# PSU.net
KiCad netlist of a schematic drawn in Altium Designer
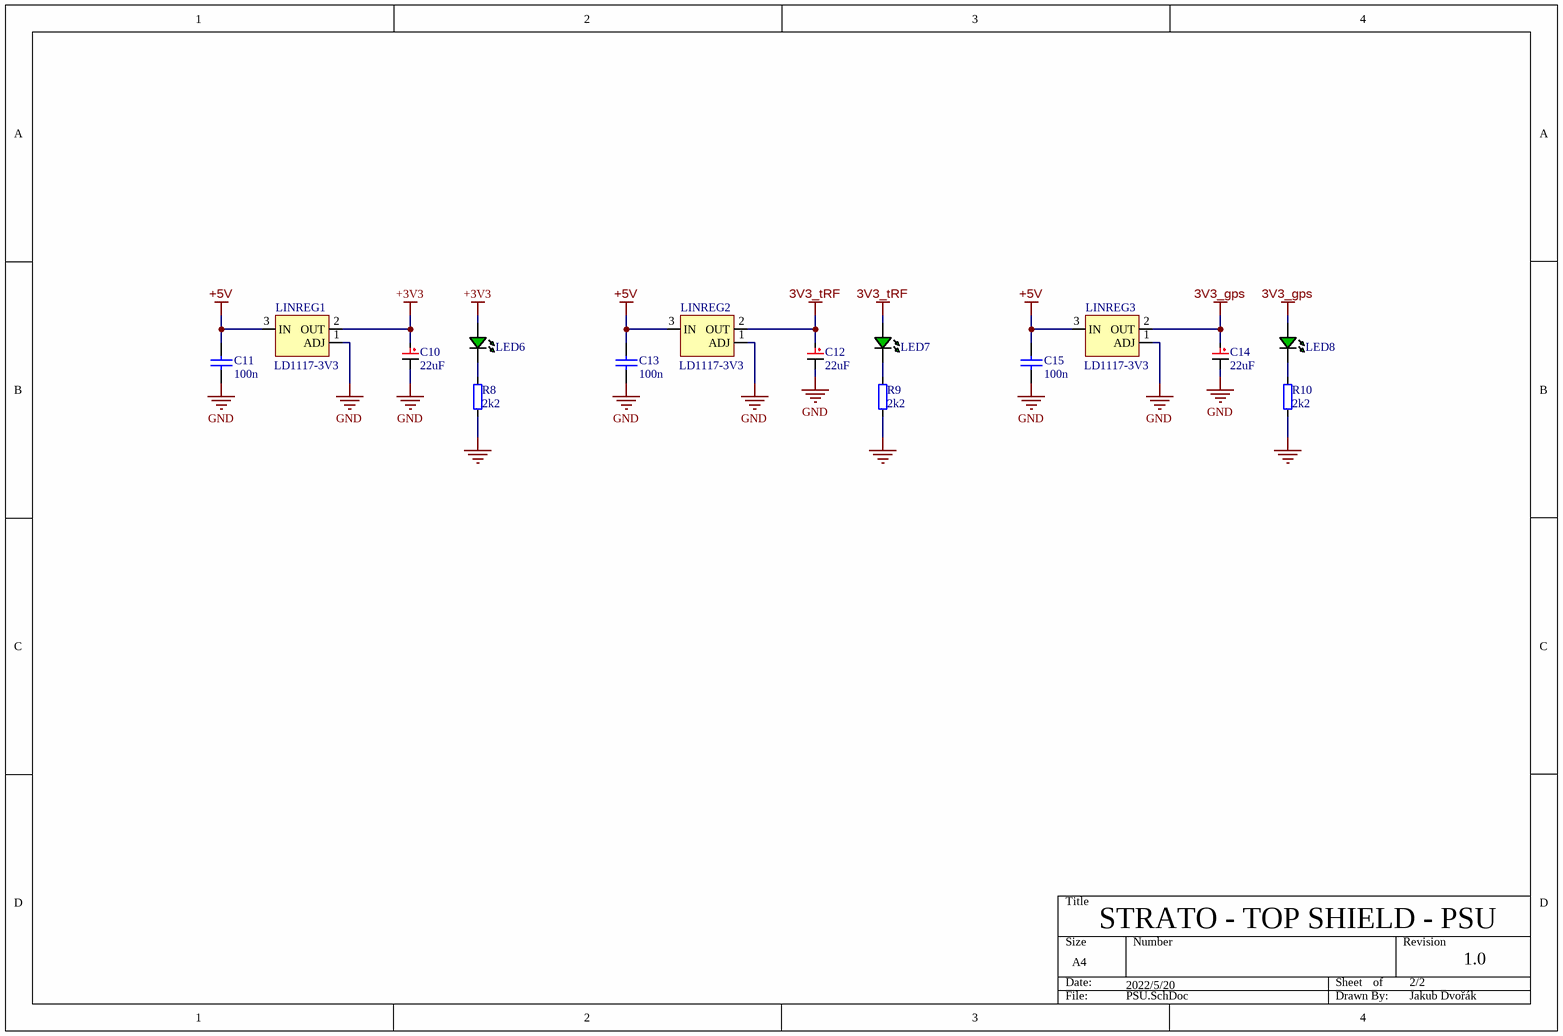
[diagram p0: PSU.SchDoc]

(export (version "E")
  (design (tool "Eeschema 10.0.6"))
  (components
    (comp (ref "C10")
      (value "22uF")
      (footprint "CAP E-CASE TANTAL")
      (description "CAPT 22u 35V case-E tatal")
      (fields
        (field (name "MANUFACTURER") "VISHAY SPRAGUE")
        (field (name "MANUFACTURER PART NUMBER") "TR3E226K035C0260")
      )
      (libsource (lib "all_in_one_library") (part "CAPT_22u_35V_E"))
    )
    (comp (ref "C11")
      (value "100n")
      (footprint "WCAP-CSGP_0603_L1.6W0.8H0.8_Reflow")
      (description "WCAP-CSGP Multilayer Ceramic Chip Capacitor, General Purpose, size 0603, X7R, 100nF, 25V")
      (fields
        (field (name "MANUFACTURER") "Wurth Elektronik")
        (field (name "MANUFACTURER PART NUMBER") "885012206071R")
      )
      (libsource (lib "Altium_WCAP-CSGP (rev22a)") (part "885012206071R"))
    )
    (comp (ref "C12")
      (value "22uF")
      (footprint "CAP E-CASE TANTAL")
      (description "CAPT 22u 35V case-E tatal")
      (fields
        (field (name "MANUFACTURER") "VISHAY SPRAGUE")
        (field (name "MANUFACTURER PART NUMBER") "TR3E226K035C0260")
      )
      (libsource (lib "all_in_one_library") (part "CAPT_22u_35V_E"))
    )
    (comp (ref "C13")
      (value "100n")
      (footprint "WCAP-CSGP_0603_L1.6W0.8H0.8_Reflow")
      (description "WCAP-CSGP Multilayer Ceramic Chip Capacitor, General Purpose, size 0603, X7R, 100nF, 25V")
      (fields
        (field (name "MANUFACTURER") "Wurth Elektronik")
        (field (name "MANUFACTURER PART NUMBER") "885012206071R")
      )
      (libsource (lib "Altium_WCAP-CSGP (rev22a)") (part "885012206071R"))
    )
    (comp (ref "C14")
      (value "22uF")
      (footprint "CAP E-CASE TANTAL")
      (description "CAPT 22u 35V case-E tatal")
      (fields
        (field (name "MANUFACTURER") "VISHAY SPRAGUE")
        (field (name "MANUFACTURER PART NUMBER") "TR3E226K035C0260")
      )
      (libsource (lib "all_in_one_library") (part "CAPT_22u_35V_E"))
    )
    (comp (ref "C15")
      (value "100n")
      (footprint "WCAP-CSGP_0603_L1.6W0.8H0.8_Reflow")
      (description "WCAP-CSGP Multilayer Ceramic Chip Capacitor, General Purpose, size 0603, X7R, 100nF, 25V")
      (fields
        (field (name "MANUFACTURER") "Wurth Elektronik")
        (field (name "MANUFACTURER PART NUMBER") "885012206071R")
      )
      (libsource (lib "Altium_WCAP-CSGP (rev22a)") (part "885012206071R"))
    )
    (comp (ref "LED6")
      (value "green")
      (footprint "0805LEDG")
      (libsource (lib "all_in_one_library") (part "LEDG_0805"))
    )
    (comp (ref "LED7")
      (value "green")
      (footprint "0805LEDG")
      (libsource (lib "all_in_one_library") (part "LEDG_0805"))
    )
    (comp (ref "LED8")
      (value "green")
      (footprint "0805LEDG")
      (libsource (lib "all_in_one_library") (part "LEDG_0805"))
    )
    (comp (ref "LINREG1")
      (value "LD1117-3V3")
      (footprint "SOT223")
      (description "15V 1A Adjustable low drop voltage regulator")
      (libsource (lib "all_in_one_library") (part "LINREG_ADJ_LM1117DT"))
    )
    (comp (ref "LINREG2")
      (value "LD1117-3V3")
      (footprint "SOT223")
      (description "15V 1A Adjustable low drop voltage regulator")
      (libsource (lib "all_in_one_library") (part "LINREG_ADJ_LM1117DT"))
    )
    (comp (ref "LINREG3")
      (value "LD1117-3V3")
      (footprint "SOT223")
      (description "15V 1A Adjustable low drop voltage regulator")
      (libsource (lib "all_in_one_library") (part "LINREG_ADJ_LM1117DT"))
    )
    (comp (ref "R8")
      (value "2k2")
      (footprint "RES_0603")
      (description "2200.00")
      (fields (field (name "Comment") "Thick film"))
      (libsource (lib "all_in_one_library") (part "RES_2k2_5%_0603"))
    )
    (comp (ref "R9")
      (value "2k2")
      (footprint "RES_0603")
      (description "2200.00")
      (fields (field (name "Comment") "Thick film"))
      (libsource (lib "all_in_one_library") (part "RES_2k2_5%_0603"))
    )
    (comp (ref "R10")
      (value "2k2")
      (footprint "RES_0603")
      (description "2200.00")
      (fields (field (name "Comment") "Thick film"))
      (libsource (lib "all_in_one_library") (part "RES_2k2_5%_0603"))
    )
  )
  (nets
    (net (code "1") (name "+3V3") (class "Default")
      (node (ref "C10") (pin "+") (pinfunction "+_+") (pintype "passive"))
      (node (ref "LED6") (pin "A") (pinfunction "A_A") (pintype "passive"))
      (node (ref "LINREG1") (pin "2") (pinfunction "OUT_2") (pintype "passive"))
    )
    (net (code "2") (name "+5V") (class "Default")
      (node (ref "C11") (pin "2") (pinfunction "2_2") (pintype "passive"))
      (node (ref "C13") (pin "2") (pinfunction "2_2") (pintype "passive"))
      (node (ref "C15") (pin "2") (pinfunction "2_2") (pintype "passive"))
      (node (ref "LINREG1") (pin "3") (pinfunction "IN_3") (pintype "passive"))
      (node (ref "LINREG2") (pin "3") (pinfunction "IN_3") (pintype "passive"))
      (node (ref "LINREG3") (pin "3") (pinfunction "IN_3") (pintype "passive"))
    )
    (net (code "3") (name "3V3_gps") (class "Default")
      (node (ref "C14") (pin "+") (pinfunction "+_+") (pintype "passive"))
      (node (ref "LED8") (pin "A") (pinfunction "A_A") (pintype "passive"))
      (node (ref "LINREG3") (pin "2") (pinfunction "OUT_2") (pintype "passive"))
    )
    (net (code "4") (name "3V3_tRF") (class "Default")
      (node (ref "C12") (pin "+") (pinfunction "+_+") (pintype "passive"))
      (node (ref "LED7") (pin "A") (pinfunction "A_A") (pintype "passive"))
      (node (ref "LINREG2") (pin "2") (pinfunction "OUT_2") (pintype "passive"))
    )
    (net (code "5") (name "GND") (class "Default")
      (node (ref "C10") (pin "-") (pinfunction "-_-") (pintype "passive"))
      (node (ref "C11") (pin "1") (pinfunction "1_1") (pintype "passive"))
      (node (ref "C12") (pin "-") (pinfunction "-_-") (pintype "passive"))
      (node (ref "C13") (pin "1") (pinfunction "1_1") (pintype "passive"))
      (node (ref "C14") (pin "-") (pinfunction "-_-") (pintype "passive"))
      (node (ref "C15") (pin "1") (pinfunction "1_1") (pintype "passive"))
      (node (ref "LINREG1") (pin "1") (pinfunction "ADJ_1") (pintype "passive"))
      (node (ref "LINREG2") (pin "1") (pinfunction "ADJ_1") (pintype "passive"))
      (node (ref "LINREG3") (pin "1") (pinfunction "ADJ_1") (pintype "passive"))
      (node (ref "R10") (pin "1") (pinfunction "1_1") (pintype "passive"))
      (node (ref "R8") (pin "1") (pinfunction "1_1") (pintype "passive"))
      (node (ref "R9") (pin "1") (pinfunction "1_1") (pintype "passive"))
    )
    (net (code "6") (name "Net-(LED6-PadK)") (class "Default")
      (node (ref "LED6") (pin "K") (pinfunction "K_K") (pintype "passive"))
      (node (ref "R8") (pin "2") (pinfunction "2_2") (pintype "passive"))
    )
    (net (code "7") (name "Net-(LED7-PadK)") (class "Default")
      (node (ref "LED7") (pin "K") (pinfunction "K_K") (pintype "passive"))
      (node (ref "R9") (pin "2") (pinfunction "2_2") (pintype "passive"))
    )
    (net (code "8") (name "Net-(LED8-PadK)") (class "Default")
      (node (ref "LED8") (pin "K") (pinfunction "K_K") (pintype "passive"))
      (node (ref "R10") (pin "2") (pinfunction "2_2") (pintype "passive"))
    )
  )
)
